# Power_MUX.net
KiCad netlist of a schematic drawn in Altium Designer
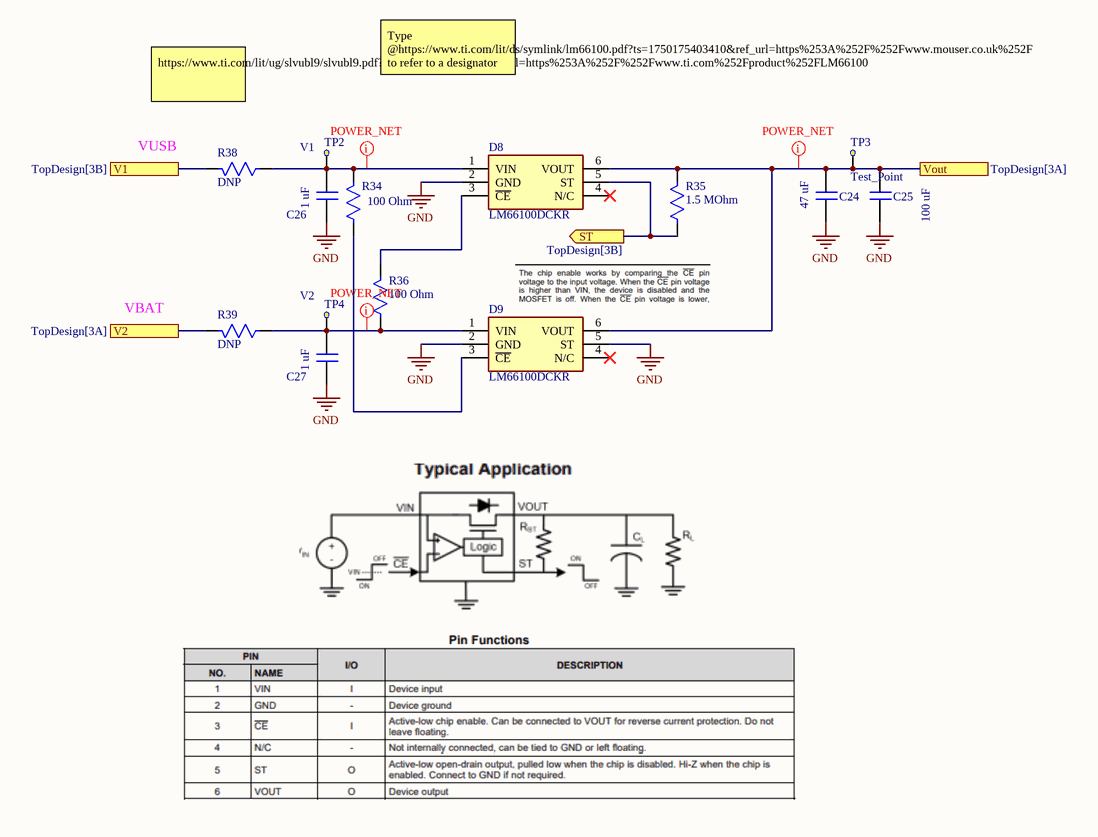
[diagram p0: Power_MUX.SchDoc]

(export (version "E")
  (design (tool "Eeschema 10.0.6"))
  (components
    (comp (ref "C24")
      (value "47 uF")
      (footprint "CAP SMD 1206")
      (description "Cap SMD.")
      (libsource (lib "Aptinex_discrete") (part "Cap SMD"))
    )
    (comp (ref "C25")
      (value "100 uF")
      (footprint "CAP SMD 1206")
      (description "Cap SMD.")
      (libsource (lib "Aptinex_discrete") (part "Cap SMD"))
    )
    (comp (ref "C26")
      (value "1 uF")
      (footprint "CAP_0603")
      (description "Cap SMD.")
      (libsource (lib "Aptinex_discrete") (part "Cap SMD"))
    )
    (comp (ref "C27")
      (value "1 uF")
      (footprint "CAP_0603")
      (description "Cap SMD.")
      (libsource (lib "Aptinex_discrete") (part "Cap SMD"))
    )
    (comp (ref "D8")
      (value "LM66100DCKR")
      (footprint "LM66100DCKR")
      (description "+/-6-V, Low IQ ideal diode with input polarity protection")
      (libsource (lib "Aptinex_devices") (part "LM66100DCKR"))
    )
    (comp (ref "D9")
      (value "LM66100DCKR")
      (footprint "LM66100DCKR")
      (description "+/-6-V, Low IQ ideal diode with input polarity protection")
      (libsource (lib "Aptinex_devices") (part "LM66100DCKR"))
    )
    (comp (ref "R34")
      (value "100 Ohm")
      (footprint "Res_0603")
      (description "SMD Resistor")
      (fields (field (name "MP") "RC0805FR-07330RL") (field (name "MF") "Yageo"))
      (libsource (lib "Aptinex_discrete") (part "Res smd"))
    )
    (comp (ref "R35")
      (value "1.5 MOhm")
      (footprint "Res_0603")
      (description "SMD Resistor")
      (fields (field (name "MP") "RC0805FR-07330RL") (field (name "MF") "Yageo"))
      (libsource (lib "Aptinex_discrete") (part "Res smd"))
    )
    (comp (ref "R36")
      (value "100 Ohm")
      (footprint "Res_0603")
      (description "SMD Resistor")
      (fields (field (name "MP") "RC0805FR-07330RL") (field (name "MF") "Yageo"))
      (libsource (lib "Aptinex_discrete") (part "Res smd"))
    )
    (comp (ref "R38")
      (value "DNP")
      (footprint "RES_0402")
      (description "SMD Resistor")
      (fields (field (name "MP") "RC0805FR-07330RL") (field (name "MF") "Yageo"))
      (libsource (lib "Aptinex_discrete") (part "Res smd"))
    )
    (comp (ref "R39")
      (value "DNP")
      (footprint "RES_0402")
      (description "SMD Resistor")
      (fields (field (name "MP") "RC0805FR-07330RL") (field (name "MF") "Yageo"))
      (libsource (lib "Aptinex_discrete") (part "Res smd"))
    )
    (comp (ref "TP2")
      (value "V1")
      (footprint "Test_Point")
      (libsource (lib "Aptinex_discrete") (part "Test_Point"))
    )
    (comp (ref "TP3")
      (value "Test_Point")
      (footprint "Test_Point")
      (libsource (lib "Aptinex_discrete") (part "Test_Point"))
    )
    (comp (ref "TP4")
      (value "V2")
      (footprint "Test_Point")
      (libsource (lib "Aptinex_discrete") (part "Test_Point"))
    )
  )
  (nets
    (net (code "1") (name "/ST") (class "Default")
      (node (ref "D8") (pin "5") (pinfunction "ST_5") (pintype "passive"))
      (node (ref "R35") (pin "2") (pinfunction "2_2") (pintype "passive"))
    )
    (net (code "2") (name "/V1") (class "Default")
      (node (ref "R38") (pin "1") (pinfunction "1_1") (pintype "passive"))
    )
    (net (code "3") (name "/V2") (class "Default")
      (node (ref "R39") (pin "1") (pinfunction "1_1") (pintype "passive"))
    )
    (net (code "4") (name "/Vout") (class "Default")
      (node (ref "C24") (pin "2") (pinfunction "2_2") (pintype "passive"))
      (node (ref "C25") (pin "2") (pinfunction "2_2") (pintype "passive"))
      (node (ref "D8") (pin "6") (pinfunction "VOUT_6") (pintype "passive"))
      (node (ref "D9") (pin "6") (pinfunction "VOUT_6") (pintype "passive"))
      (node (ref "R35") (pin "1") (pinfunction "1_1") (pintype "passive"))
      (node (ref "TP3") (pin "TP?") (pinfunction "Ref_Point_TP?") (pintype "passive"))
    )
    (net (code "5") (name "GND") (class "Default")
      (node (ref "C24") (pin "1") (pinfunction "1_1") (pintype "passive"))
      (node (ref "C25") (pin "1") (pinfunction "1_1") (pintype "passive"))
      (node (ref "C26") (pin "1") (pinfunction "1_1") (pintype "passive"))
      (node (ref "C27") (pin "1") (pinfunction "1_1") (pintype "passive"))
      (node (ref "D8") (pin "2") (pinfunction "GND_2") (pintype "passive"))
      (node (ref "D9") (pin "2") (pinfunction "GND_2") (pintype "passive"))
      (node (ref "D9") (pin "5") (pinfunction "ST_5") (pintype "passive"))
    )
    (net (code "6") (name "Net-(D8-VIN)") (class "Default")
      (node (ref "C26") (pin "2") (pinfunction "2_2") (pintype "passive"))
      (node (ref "D8") (pin "1") (pinfunction "VIN_1") (pintype "passive"))
      (node (ref "R34") (pin "1") (pinfunction "1_1") (pintype "passive"))
      (node (ref "R38") (pin "2") (pinfunction "2_2") (pintype "passive"))
      (node (ref "TP2") (pin "TP?") (pinfunction "Ref_Point_TP?") (pintype "passive"))
    )
    (net (code "7") (name "Net-(D8-~{CE})") (class "Default")
      (node (ref "D8") (pin "3") (pinfunction "~{CE}_3") (pintype "passive"))
      (node (ref "R36") (pin "1") (pinfunction "1_1") (pintype "passive"))
    )
    (net (code "8") (name "Net-(D9-VIN)") (class "Default")
      (node (ref "C27") (pin "2") (pinfunction "2_2") (pintype "passive"))
      (node (ref "D9") (pin "1") (pinfunction "VIN_1") (pintype "passive"))
      (node (ref "R36") (pin "2") (pinfunction "2_2") (pintype "passive"))
      (node (ref "R39") (pin "2") (pinfunction "2_2") (pintype "passive"))
      (node (ref "TP4") (pin "TP?") (pinfunction "Ref_Point_TP?") (pintype "passive"))
    )
    (net (code "9") (name "Net-(D9-~{CE})") (class "Default")
      (node (ref "D9") (pin "3") (pinfunction "~{CE}_3") (pintype "passive"))
      (node (ref "R34") (pin "2") (pinfunction "2_2") (pintype "passive"))
    )
    (net (code "10") (name "unconnected-(D8-N{slash}C-Pad4)") (class "Default")
      (node (ref "D8") (pin "4") (pinfunction "N/C_4") (pintype "passive+no_connect"))
    )
    (net (code "11") (name "unconnected-(D9-N{slash}C-Pad4)") (class "Default")
      (node (ref "D9") (pin "4") (pinfunction "N/C_4") (pintype "passive+no_connect"))
    )
  )
)
